# 406MHz_detector.net
KiCad netlist of a schematic drawn in EAGLE
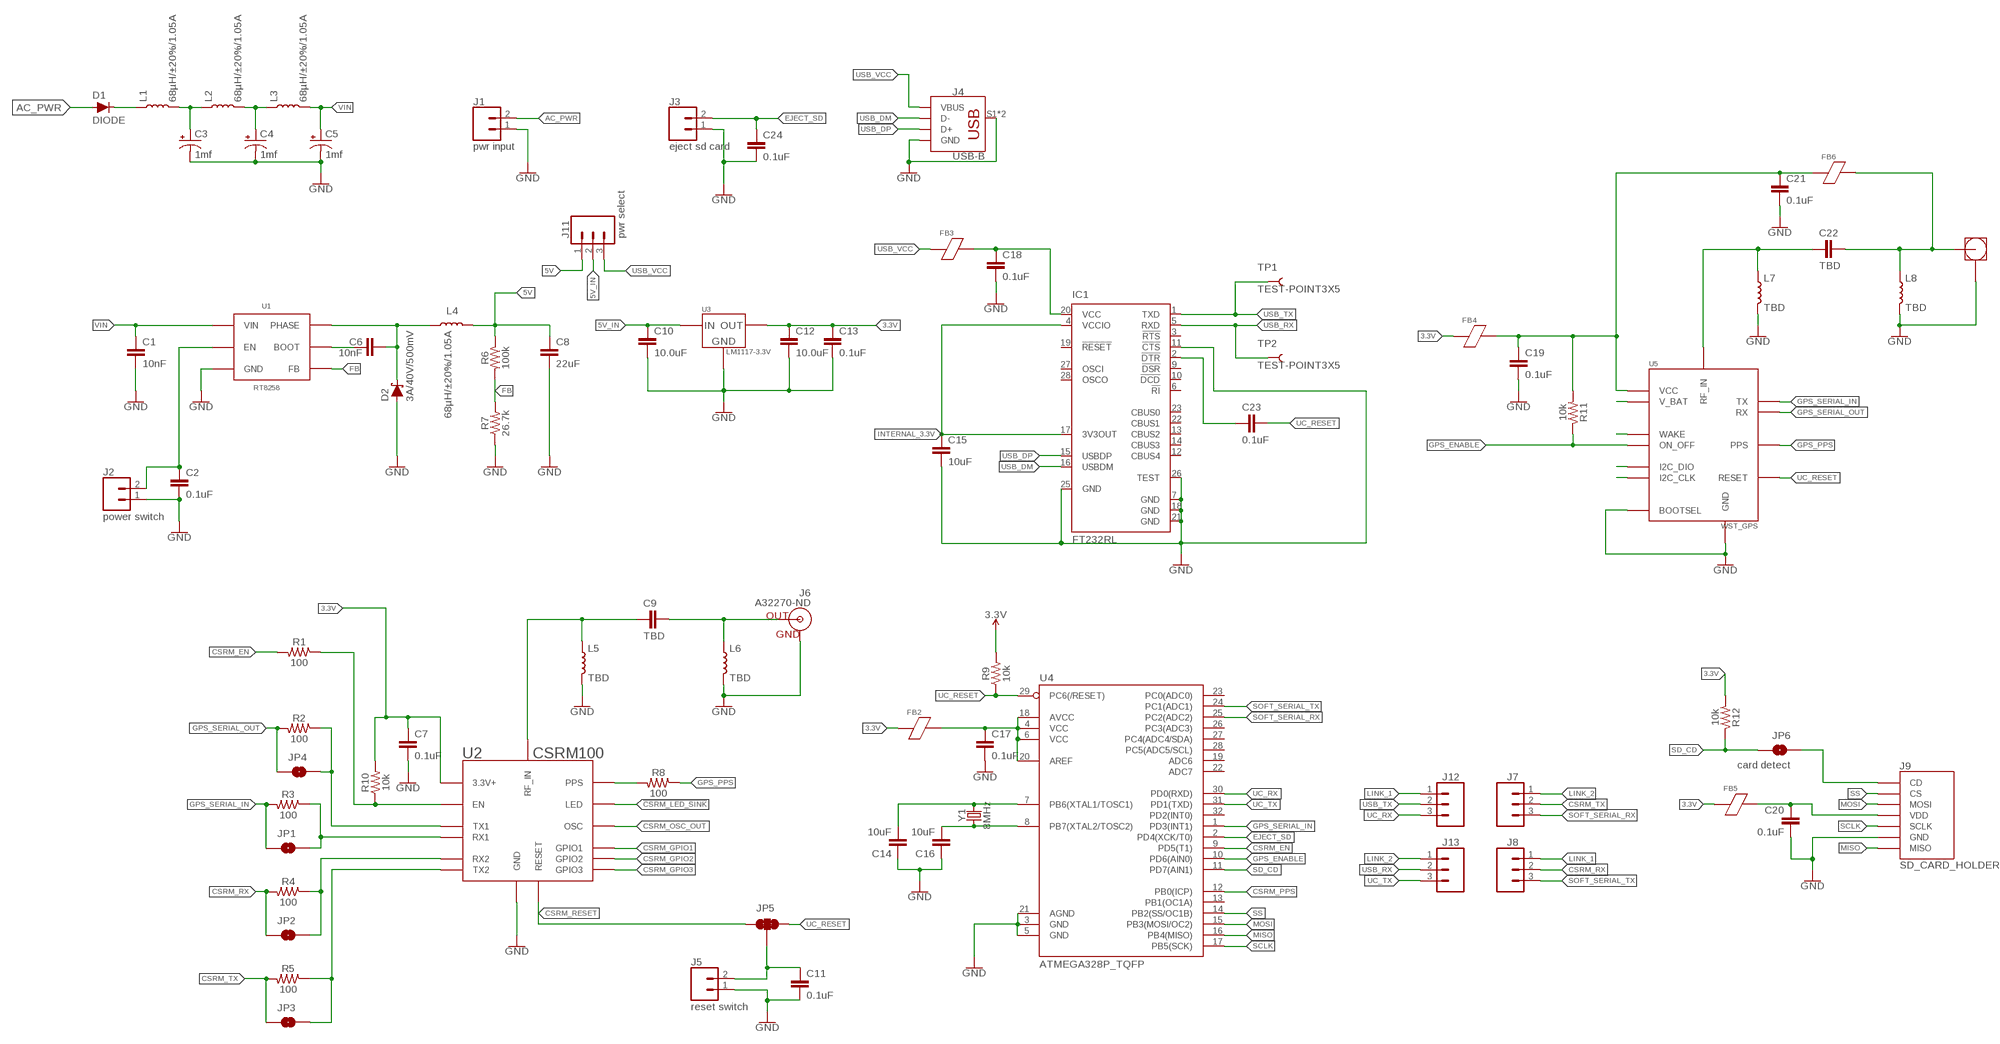
[diagram p0: schematic, sheet 1]

(export (version "E")
  (design (tool "Eeschema 10.0.6"))
  (components
    (comp (ref "C1")
      (value "10nF")
      (footprint "eagle-import:0603")
      (libsource (lib "eagle-import") (part "10NF-0603-50V-10%"))
    )
    (comp (ref "C2")
      (value "0.1uF")
      (footprint "eagle-import:0603")
      (libsource (lib "eagle-import") (part "0.18UF-0603-10V-10%"))
    )
    (comp (ref "C3")
      (value "1mf")
      (footprint "eagle-import:CPOL-RADIAL-5MM-10MM-KIT")
      (libsource (lib "eagle-import") (part "1000UF-RADIAL-5MM-35V-20%-KIT"))
    )
    (comp (ref "C4")
      (value "1mf")
      (footprint "eagle-import:CPOL-RADIAL-5MM-10MM-KIT")
      (libsource (lib "eagle-import") (part "1000UF-RADIAL-5MM-35V-20%-KIT"))
    )
    (comp (ref "C5")
      (value "1mf")
      (footprint "eagle-import:CPOL-RADIAL-5MM-10MM-KIT")
      (libsource (lib "eagle-import") (part "1000UF-RADIAL-5MM-35V-20%-KIT"))
    )
    (comp (ref "C6")
      (value "10nF")
      (footprint "eagle-import:0603")
      (libsource (lib "eagle-import") (part "10NF-0603-50V-10%"))
    )
    (comp (ref "C7")
      (value "0.1uF")
      (footprint "eagle-import:0603")
      (libsource (lib "eagle-import") (part "0.18UF-0603-10V-10%"))
    )
    (comp (ref "C8")
      (value "22uF")
      (footprint "eagle-import:0603")
      (libsource (lib "eagle-import") (part "0.18UF-0603-10V-10%"))
    )
    (comp (ref "C9")
      (value "TBD")
      (footprint "eagle-import:0603")
      (libsource (lib "eagle-import") (part "0.1UF-0603-25V-5%"))
    )
    (comp (ref "C10")
      (value "10.0uF")
      (footprint "eagle-import:1206")
      (libsource (lib "eagle-import") (part "1.0UF-1206-50V-10%"))
    )
    (comp (ref "C11")
      (value "0.1uF")
      (footprint "eagle-import:0603")
      (libsource (lib "eagle-import") (part "0.18UF-0603-10V-10%"))
    )
    (comp (ref "C12")
      (value "10.0uF")
      (footprint "eagle-import:1206")
      (libsource (lib "eagle-import") (part "1.0UF-1206-50V-10%"))
    )
    (comp (ref "C13")
      (value "0.1uF")
      (footprint "eagle-import:0603")
      (libsource (lib "eagle-import") (part "0.18UF-0603-10V-10%"))
    )
    (comp (ref "C14")
      (value "10uF")
      (footprint "eagle-import:1206")
      (libsource (lib "eagle-import") (part "10UF-1206-6.3V-20%"))
    )
    (comp (ref "C15")
      (value "10uF")
      (footprint "eagle-import:1206")
      (libsource (lib "eagle-import") (part "10UF-1206-6.3V-20%"))
    )
    (comp (ref "C16")
      (value "10uF")
      (footprint "eagle-import:1206")
      (libsource (lib "eagle-import") (part "10UF-1206-6.3V-20%"))
    )
    (comp (ref "C17")
      (value "0.1uF")
      (footprint "eagle-import:0603")
      (libsource (lib "eagle-import") (part "0.18UF-0603-10V-10%"))
    )
    (comp (ref "C18")
      (value "0.1uF")
      (footprint "eagle-import:0603")
      (libsource (lib "eagle-import") (part "0.18UF-0603-10V-10%"))
    )
    (comp (ref "C19")
      (value "0.1uF")
      (footprint "eagle-import:0603")
      (libsource (lib "eagle-import") (part "0.18UF-0603-10V-10%"))
    )
    (comp (ref "C20")
      (value "0.1uF")
      (footprint "eagle-import:0603")
      (libsource (lib "eagle-import") (part "0.18UF-0603-10V-10%"))
    )
    (comp (ref "C21")
      (value "0.1uF")
      (footprint "eagle-import:0603")
      (libsource (lib "eagle-import") (part "0.18UF-0603-10V-10%"))
    )
    (comp (ref "C22")
      (value "TBD")
      (footprint "eagle-import:0603")
      (libsource (lib "eagle-import") (part "0.1UF-0603-25V-5%"))
    )
    (comp (ref "C23")
      (value "0.1uF")
      (footprint "eagle-import:0603")
      (libsource (lib "eagle-import") (part "0.18UF-0603-10V-10%"))
    )
    (comp (ref "C24")
      (value "0.1uF")
      (footprint "eagle-import:0603")
      (libsource (lib "eagle-import") (part "0.18UF-0603-10V-10%"))
    )
    (comp (ref "D1")
      (value "DIODE")
      (footprint "eagle-import:SMA-DIODE")
      (libsource (lib "eagle-import") (part "DIODE"))
    )
    (comp (ref "D2")
      (value "3A/40V/500mV")
      (footprint "eagle-import:SMA-DIODE")
      (libsource (lib "eagle-import") (part "DIODE-SCHOTTKY-B340A"))
    )
    (comp (ref "FB2")
      (value "FERRITE_BEAD")
      (footprint "eagle-import:0603")
      (libsource (lib "eagle-import") (part "FERRITE_BEAD"))
    )
    (comp (ref "FB3")
      (value "FERRITE_BEAD")
      (footprint "eagle-import:0603")
      (libsource (lib "eagle-import") (part "FERRITE_BEAD"))
    )
    (comp (ref "FB4")
      (value "FERRITE_BEAD")
      (footprint "eagle-import:0603")
      (libsource (lib "eagle-import") (part "FERRITE_BEAD"))
    )
    (comp (ref "FB5")
      (value "FERRITE_BEAD")
      (footprint "eagle-import:0603")
      (libsource (lib "eagle-import") (part "FERRITE_BEAD"))
    )
    (comp (ref "FB6")
      (value "FERRITE_BEAD")
      (footprint "eagle-import:0603")
      (libsource (lib "eagle-import") (part "FERRITE_BEAD"))
    )
    (comp (ref "IC1")
      (value "FT232RL")
      (footprint "eagle-import:SSOP28")
      (libsource (lib "eagle-import") (part "FT232RL"))
    )
    (comp (ref "J1")
      (value "pwr input")
      (footprint "eagle-import:1X02_LOCK")
      (libsource (lib "eagle-import") (part "CONN_02LOCK"))
    )
    (comp (ref "J2")
      (value "power switch")
      (footprint "eagle-import:1X02")
      (libsource (lib "eagle-import") (part "CONN_02"))
    )
    (comp (ref "J3")
      (value "eject sd card")
      (footprint "eagle-import:1X02")
      (libsource (lib "eagle-import") (part "CONN_02"))
    )
    (comp (ref "J4")
      (value "USB-B")
      (footprint "eagle-import:USB")
      (libsource (lib "eagle-import") (part "USB-B"))
    )
    (comp (ref "J5")
      (value "reset switch")
      (footprint "eagle-import:1X02")
      (libsource (lib "eagle-import") (part "CONN_02"))
    )
    (comp (ref "J6")
      (value "A32270-ND")
      (footprint "eagle-import:A33270-ND")
      (libsource (lib "eagle-import") (part "A32270-ND"))
    )
    (comp (ref "J7")
      (value "select jumper")
      (footprint "eagle-import:1X03_LOCK")
      (libsource (lib "eagle-import") (part "CONN_03LOCK"))
    )
    (comp (ref "J8")
      (value "select jumper")
      (footprint "eagle-import:1X03_LOCK")
      (libsource (lib "eagle-import") (part "CONN_03LOCK"))
    )
    (comp (ref "J9")
      (value "SD_CARD_HOLDER")
      (footprint "eagle-import:SD_CARD_HOLDER")
      (libsource (lib "eagle-import") (part "SD_CARD_HOLDER"))
    )
    (comp (ref "J10")
      (value "SMA")
      (footprint "eagle-import:SMA_R_A")
      (libsource (lib "eagle-import") (part "SMA"))
    )
    (comp (ref "J11")
      (value "pwr select")
      (footprint "eagle-import:1X03_LOCK")
      (libsource (lib "eagle-import") (part "CONN_03LOCK"))
    )
    (comp (ref "J12")
      (value "select jumper")
      (footprint "eagle-import:1X03_LOCK")
      (libsource (lib "eagle-import") (part "CONN_03LOCK"))
    )
    (comp (ref "J13")
      (value "select jumper")
      (footprint "eagle-import:1X03_LOCK")
      (libsource (lib "eagle-import") (part "CONN_03LOCK"))
    )
    (comp (ref "JP1")
      (value "JUMPER-SMT_2_NO_SILK_ROUND")
      (footprint "eagle-import:SMT-JUMPER_2_NO_SILK_ROUND")
      (libsource (lib "eagle-import") (part "JUMPER-SMT_2_NO_SILK_ROUND"))
    )
    (comp (ref "JP2")
      (value "JUMPER-SMT_2_NO_SILK_ROUND")
      (footprint "eagle-import:SMT-JUMPER_2_NO_SILK_ROUND")
      (libsource (lib "eagle-import") (part "JUMPER-SMT_2_NO_SILK_ROUND"))
    )
    (comp (ref "JP3")
      (value "JUMPER-SMT_2_NO_SILK_ROUND")
      (footprint "eagle-import:SMT-JUMPER_2_NO_SILK_ROUND")
      (libsource (lib "eagle-import") (part "JUMPER-SMT_2_NO_SILK_ROUND"))
    )
    (comp (ref "JP4")
      (value "JUMPER-SMT_2_NO_SILK_ROUND")
      (footprint "eagle-import:SMT-JUMPER_2_NO_SILK_ROUND")
      (libsource (lib "eagle-import") (part "JUMPER-SMT_2_NO_SILK_ROUND"))
    )
    (comp (ref "JP5")
      (value "JUMPER-SMT_3_2-NC_TRACE_SILK")
      (footprint "eagle-import:SMT-JUMPER_3_2-NC_TRACE_SILK")
      (libsource (lib "eagle-import") (part "JUMPER-SMT_3_2-NC_TRACE_SILK"))
    )
    (comp (ref "JP6")
      (value "card detect")
      (footprint "eagle-import:SMT-JUMPER_2_NO_SILK")
      (libsource (lib "eagle-import") (part "JUMPER-SMT_2_NO_SILK"))
    )
    (comp (ref "L1")
      (value "68µH/±20%/1.05A")
      (footprint "eagle-import:CR75")
      (libsource (lib "eagle-import") (part "INDUCTOR-CR75-68UH"))
    )
    (comp (ref "L2")
      (value "68µH/±20%/1.05A")
      (footprint "eagle-import:CR75")
      (libsource (lib "eagle-import") (part "INDUCTOR-CR75-68UH"))
    )
    (comp (ref "L3")
      (value "68µH/±20%/1.05A")
      (footprint "eagle-import:CR75")
      (libsource (lib "eagle-import") (part "INDUCTOR-CR75-68UH"))
    )
    (comp (ref "L4")
      (value "68µH/±20%/1.05A")
      (footprint "eagle-import:CR75")
      (libsource (lib "eagle-import") (part "INDUCTOR-CR75-68UH"))
    )
    (comp (ref "L5")
      (value "TBD")
      (footprint "eagle-import:0603")
      (libsource (lib "eagle-import") (part "INDUCTOR-0603-33NH"))
    )
    (comp (ref "L6")
      (value "TBD")
      (footprint "eagle-import:0603")
      (libsource (lib "eagle-import") (part "INDUCTOR-0603-33NH"))
    )
    (comp (ref "L7")
      (value "TBD")
      (footprint "eagle-import:0603")
      (libsource (lib "eagle-import") (part "INDUCTOR-0603-33NH"))
    )
    (comp (ref "L8")
      (value "TBD")
      (footprint "eagle-import:0603")
      (libsource (lib "eagle-import") (part "INDUCTOR-0603-33NH"))
    )
    (comp (ref "R1")
      (value "100")
      (footprint "eagle-import:0603")
      (libsource (lib "eagle-import") (part "10KOHM-0603-1/10W-1%"))
    )
    (comp (ref "R2")
      (value "100")
      (footprint "eagle-import:0603")
      (libsource (lib "eagle-import") (part "10KOHM-0603-1/10W-1%"))
    )
    (comp (ref "R3")
      (value "100")
      (footprint "eagle-import:0603")
      (libsource (lib "eagle-import") (part "10KOHM-0603-1/10W-1%"))
    )
    (comp (ref "R4")
      (value "100")
      (footprint "eagle-import:0603")
      (libsource (lib "eagle-import") (part "10KOHM-0603-1/10W-1%"))
    )
    (comp (ref "R5")
      (value "100")
      (footprint "eagle-import:0603")
      (libsource (lib "eagle-import") (part "10KOHM-0603-1/10W-1%"))
    )
    (comp (ref "R6")
      (value "100k")
      (footprint "eagle-import:0603")
      (libsource (lib "eagle-import") (part "10KOHM-0603-1/10W-1%"))
    )
    (comp (ref "R7")
      (value "26.7k")
      (footprint "eagle-import:0603")
      (libsource (lib "eagle-import") (part "26.7KOHM0603-1/10W-1%"))
    )
    (comp (ref "R8")
      (value "100")
      (footprint "eagle-import:0603")
      (libsource (lib "eagle-import") (part "10KOHM-0603-1/10W-1%"))
    )
    (comp (ref "R9")
      (value "10k")
      (footprint "eagle-import:0603")
      (libsource (lib "eagle-import") (part "10KOHM-0603-1/10W-1%"))
    )
    (comp (ref "R10")
      (value "10k")
      (footprint "eagle-import:0603")
      (libsource (lib "eagle-import") (part "10KOHM-0603-1/10W-1%"))
    )
    (comp (ref "R11")
      (value "10k")
      (footprint "eagle-import:0603")
      (libsource (lib "eagle-import") (part "10KOHM-0603-1/10W-1%"))
    )
    (comp (ref "R12")
      (value "10k")
      (footprint "eagle-import:0603")
      (libsource (lib "eagle-import") (part "10KOHM-0603-1/10W-1%"))
    )
    (comp (ref "TP1")
      (value "TEST-POINT3X5")
      (footprint "eagle-import:PAD.03X.05")
      (libsource (lib "eagle-import") (part "TEST-POINT3X5"))
    )
    (comp (ref "TP2")
      (value "TEST-POINT3X5")
      (footprint "eagle-import:PAD.03X.05")
      (libsource (lib "eagle-import") (part "TEST-POINT3X5"))
    )
    (comp (ref "U1")
      (value "RT8258")
      (footprint "eagle-import:SOT23-6")
      (libsource (lib "eagle-import") (part "RT8258"))
    )
    (comp (ref "U2")
      (value "CSRM100")
      (footprint "eagle-import:CSRM")
      (libsource (lib "eagle-import") (part "CSRM100"))
    )
    (comp (ref "U3")
      (value "LM1117-3.3V")
      (footprint "eagle-import:SOT223")
      (libsource (lib "eagle-import") (part "LM1117-3.3V"))
    )
    (comp (ref "U4")
      (value "ATMEGA328P_TQFP")
      (footprint "eagle-import:TQFP32-08")
      (libsource (lib "eagle-import") (part "ATMEGA328P_TQFP"))
    )
    (comp (ref "U5")
      (value "WST_GPS")
      (footprint "eagle-import:WST_GPS")
      (libsource (lib "eagle-import") (part "WST_GPS"))
    )
    (comp (ref "Y1")
      (value "8MHz")
      (footprint "eagle-import:HC49UP")
      (libsource (lib "eagle-import") (part "CRYSTAL-8MHZSMD-HC49UP"))
    )
  )
  (nets
    (net (code "1") (name "/~{CSRM_LED_SINK}") (class "Default")
      (node (ref "U2") (pin "LED") (pinfunction "LED_LED") (pintype "bidirectional"))
    )
    (net (code "2") (name "3.3V") (class "Default")
      (node (ref "C12") (pin "1") (pinfunction "1_1") (pintype "passive"))
      (node (ref "C13") (pin "1") (pinfunction "1_1") (pintype "passive"))
      (node (ref "C7") (pin "1") (pinfunction "1_1") (pintype "passive"))
      (node (ref "FB2") (pin "1") (pinfunction "P$1_1") (pintype "bidirectional"))
      (node (ref "FB4") (pin "1") (pinfunction "P$1_1") (pintype "bidirectional"))
      (node (ref "FB5") (pin "1") (pinfunction "P$1_1") (pintype "bidirectional"))
      (node (ref "R10") (pin "2") (pinfunction "2_2") (pintype "passive"))
      (node (ref "R12") (pin "2") (pinfunction "2_2") (pintype "passive"))
      (node (ref "R9") (pin "2") (pinfunction "2_2") (pintype "passive"))
      (node (ref "U2") (pin "PWR_IN") (pinfunction "3.3V+_PWR_IN") (pintype "bidirectional"))
      (node (ref "U3") (pin "2") (pinfunction "VOUT_2") (pintype "bidirectional"))
      (node (ref "U3") (pin "4") (pinfunction "VOUT_4") (pintype "bidirectional"))
    )
    (net (code "3") (name "5V") (class "Default")
      (node (ref "C8") (pin "1") (pinfunction "1_1") (pintype "passive"))
      (node (ref "J11") (pin "1") (pinfunction "1_1") (pintype "passive"))
      (node (ref "L4") (pin "P$2") (pinfunction "2_P$2") (pintype "passive"))
      (node (ref "R6") (pin "1") (pinfunction "1_1") (pintype "passive"))
    )
    (net (code "4") (name "5V_IN") (class "Default")
      (node (ref "C10") (pin "1") (pinfunction "1_1") (pintype "passive"))
      (node (ref "J11") (pin "2") (pinfunction "2_2") (pintype "passive"))
      (node (ref "U3") (pin "3") (pinfunction "VIN_3") (pintype "bidirectional"))
    )
    (net (code "5") (name "AC_PWR") (class "Default")
      (node (ref "D1") (pin "A") (pinfunction "A_A") (pintype "passive"))
      (node (ref "J1") (pin "2") (pinfunction "2_2") (pintype "passive"))
    )
    (net (code "6") (name "CSRM_EN") (class "Default")
      (node (ref "R1") (pin "2") (pinfunction "2_2") (pintype "passive"))
      (node (ref "U4") (pin "9") (pinfunction "PD5(T1)_9") (pintype "bidirectional"))
    )
    (net (code "7") (name "CSRM_GPIO1") (class "Default")
      (node (ref "U2") (pin "GPIO1") (pinfunction "GPIO1_GPIO1") (pintype "bidirectional"))
    )
    (net (code "8") (name "CSRM_GPIO2") (class "Default")
      (node (ref "U2") (pin "GPIO2") (pinfunction "GPIO2_GPIO2") (pintype "bidirectional"))
    )
    (net (code "9") (name "CSRM_GPIO3") (class "Default")
      (node (ref "U2") (pin "GPIO3") (pinfunction "GPIO3_GPIO3") (pintype "bidirectional"))
    )
    (net (code "10") (name "CSRM_OSC_OUT") (class "Default")
      (node (ref "U2") (pin "OSC_OUT") (pinfunction "OSC_OSC_OUT") (pintype "bidirectional"))
    )
    (net (code "11") (name "CSRM_PPS") (class "Default")
      (node (ref "R8") (pin "2") (pinfunction "2_2") (pintype "passive"))
      (node (ref "U2") (pin "PPS") (pinfunction "PPS_PPS") (pintype "bidirectional"))
      (node (ref "U4") (pin "12") (pinfunction "PB0(ICP)_12") (pintype "bidirectional"))
    )
    (net (code "12") (name "CSRM_RESET") (class "Default")
      (node (ref "JP5") (pin "1") (pinfunction "1_1") (pintype "passive"))
      (node (ref "U2") (pin "_RESET") (pinfunction "RESET__RESET") (pintype "bidirectional"))
    )
    (net (code "13") (name "CSRM_RX") (class "Default")
      (node (ref "J8") (pin "2") (pinfunction "2_2") (pintype "passive"))
      (node (ref "JP2") (pin "1") (pinfunction "1_1") (pintype "passive"))
      (node (ref "R4") (pin "2") (pinfunction "2_2") (pintype "passive"))
    )
    (net (code "14") (name "CSRM_TX") (class "Default")
      (node (ref "J7") (pin "2") (pinfunction "2_2") (pintype "passive"))
      (node (ref "JP3") (pin "1") (pinfunction "1_1") (pintype "passive"))
      (node (ref "R5") (pin "2") (pinfunction "2_2") (pintype "passive"))
    )
    (net (code "15") (name "EJECT_SD") (class "Default")
      (node (ref "C24") (pin "1") (pinfunction "1_1") (pintype "passive"))
      (node (ref "J3") (pin "2") (pinfunction "2_2") (pintype "passive"))
      (node (ref "U4") (pin "2") (pinfunction "PD4(XCK/T0)_2") (pintype "bidirectional"))
    )
    (net (code "16") (name "FB") (class "Default")
      (node (ref "R6") (pin "2") (pinfunction "2_2") (pintype "passive"))
      (node (ref "R7") (pin "2") (pinfunction "2_2") (pintype "passive"))
      (node (ref "U1") (pin "3") (pinfunction "FB_3") (pintype "bidirectional"))
    )
    (net (code "17") (name "GND") (class "Default")
      (node (ref "C1") (pin "2") (pinfunction "2_2") (pintype "passive"))
      (node (ref "C10") (pin "2") (pinfunction "2_2") (pintype "passive"))
      (node (ref "C11") (pin "2") (pinfunction "2_2") (pintype "passive"))
      (node (ref "C12") (pin "2") (pinfunction "2_2") (pintype "passive"))
      (node (ref "C13") (pin "2") (pinfunction "2_2") (pintype "passive"))
      (node (ref "C14") (pin "1") (pinfunction "1_1") (pintype "passive"))
      (node (ref "C15") (pin "2") (pinfunction "2_2") (pintype "passive"))
      (node (ref "C16") (pin "1") (pinfunction "1_1") (pintype "passive"))
      (node (ref "C17") (pin "2") (pinfunction "2_2") (pintype "passive"))
      (node (ref "C18") (pin "2") (pinfunction "2_2") (pintype "passive"))
      (node (ref "C19") (pin "2") (pinfunction "2_2") (pintype "passive"))
      (node (ref "C2") (pin "2") (pinfunction "2_2") (pintype "passive"))
      (node (ref "C20") (pin "2") (pinfunction "2_2") (pintype "passive"))
      (node (ref "C21") (pin "2") (pinfunction "2_2") (pintype "passive"))
      (node (ref "C24") (pin "2") (pinfunction "2_2") (pintype "passive"))
      (node (ref "C3") (pin "-") (pinfunction "-_-") (pintype "passive"))
      (node (ref "C4") (pin "-") (pinfunction "-_-") (pintype "passive"))
      (node (ref "C5") (pin "-") (pinfunction "-_-") (pintype "passive"))
      (node (ref "C7") (pin "2") (pinfunction "2_2") (pintype "passive"))
      (node (ref "C8") (pin "2") (pinfunction "2_2") (pintype "passive"))
      (node (ref "D2") (pin "A") (pinfunction "A_A") (pintype "passive"))
      (node (ref "IC1") (pin "11") (pinfunction "~{CTS}_11") (pintype "input"))
      (node (ref "IC1") (pin "18") (pinfunction "GND_18") (pintype "power_in"))
      (node (ref "IC1") (pin "21") (pinfunction "GND_21") (pintype "power_in"))
      (node (ref "IC1") (pin "25") (pinfunction "GND_25") (pintype "power_in"))
      (node (ref "IC1") (pin "26") (pinfunction "TEST_26") (pintype "input"))
      (node (ref "IC1") (pin "7") (pinfunction "GND_7") (pintype "power_in"))
      (node (ref "J1") (pin "1") (pinfunction "1_1") (pintype "passive"))
      (node (ref "J10") (pin "P$2") (pinfunction "P$2_P$2") (pintype "bidirectional"))
      (node (ref "J10") (pin "P$3") (pinfunction "P$2_P$3") (pintype "bidirectional"))
      (node (ref "J10") (pin "P$4") (pinfunction "P$2_P$4") (pintype "bidirectional"))
      (node (ref "J10") (pin "P$5") (pinfunction "P$2_P$5") (pintype "bidirectional"))
      (node (ref "J2") (pin "1") (pinfunction "1_1") (pintype "passive"))
      (node (ref "J3") (pin "1") (pinfunction "1_1") (pintype "passive"))
      (node (ref "J4") (pin "4") (pinfunction "GND_4") (pintype "power_in"))
      (node (ref "J4") (pin "S1") (pinfunction "SHIELD_S1") (pintype "bidirectional"))
      (node (ref "J4") (pin "S2") (pinfunction "SHIELD_S2") (pintype "bidirectional"))
      (node (ref "J5") (pin "1") (pinfunction "1_1") (pintype "passive"))
      (node (ref "J6") (pin "GND1") (pinfunction "GND_GND1") (pintype "bidirectional"))
      (node (ref "J6") (pin "GND2") (pinfunction "GND_GND2") (pintype "bidirectional"))
      (node (ref "J6") (pin "GND3") (pinfunction "GND_GND3") (pintype "bidirectional"))
      (node (ref "J6") (pin "GND4") (pinfunction "GND_GND4") (pintype "bidirectional"))
      (node (ref "J9") (pin "GND1") (pinfunction "GND_GND1") (pintype "bidirectional"))
      (node (ref "J9") (pin "GND2") (pinfunction "GND_GND2") (pintype "bidirectional"))
      (node (ref "J9") (pin "P6") (pinfunction "GND_P6") (pintype "bidirectional"))
      (node (ref "L5") (pin "2") (pinfunction "2_2") (pintype "passive"))
      (node (ref "L6") (pin "2") (pinfunction "2_2") (pintype "passive"))
      (node (ref "L7") (pin "2") (pinfunction "2_2") (pintype "passive"))
      (node (ref "L8") (pin "2") (pinfunction "2_2") (pintype "passive"))
      (node (ref "R7") (pin "1") (pinfunction "1_1") (pintype "passive"))
      (node (ref "U1") (pin "2") (pinfunction "GND_2") (pintype "bidirectional"))
      (node (ref "U2") (pin "GND") (pinfunction "GND_GND") (pintype "bidirectional"))
      (node (ref "U2") (pin "GND1") (pinfunction "GND_GND1") (pintype "bidirectional"))
      (node (ref "U2") (pin "GND2") (pinfunction "GND_GND2") (pintype "bidirectional"))
      (node (ref "U2") (pin "GND3") (pinfunction "GND_GND3") (pintype "bidirectional"))
      (node (ref "U2") (pin "GND4") (pinfunction "GND_GND4") (pintype "bidirectional"))
      (node (ref "U3") (pin "1") (pinfunction "GND_1") (pintype "bidirectional"))
      (node (ref "U4") (pin "21") (pinfunction "AGND_21") (pintype "bidirectional"))
      (node (ref "U4") (pin "3") (pinfunction "GND_3") (pintype "bidirectional"))
      (node (ref "U4") (pin "5") (pinfunction "GND_5") (pintype "bidirectional"))
      (node (ref "U5") (pin "P$1") (pinfunction "GND_P$1") (pintype "bidirectional"))
      (node (ref "U5") (pin "P$17") (pinfunction "GND_P$17") (pintype "bidirectional"))
      (node (ref "U5") (pin "P$18") (pinfunction "GND_P$18") (pintype "bidirectional"))
      (node (ref "U5") (pin "P$19") (pinfunction "GND_P$19") (pintype "bidirectional"))
      (node (ref "U5") (pin "P$3") (pinfunction "GND_P$3") (pintype "bidirectional"))
      (node (ref "U5") (pin "P$9") (pinfunction "BOOTSEL_P$9") (pintype "bidirectional"))
    )
    (net (code "18") (name "GPS_ENABLE") (class "Default")
      (node (ref "R11") (pin "1") (pinfunction "1_1") (pintype "passive"))
      (node (ref "U4") (pin "10") (pinfunction "PD6(AIN0)_10") (pintype "bidirectional"))
      (node (ref "U5") (pin "P$15") (pinfunction "ON_OFF_P$15") (pintype "bidirectional"))
    )
    (net (code "19") (name "GPS_PPS") (class "Default")
      (node (ref "R8") (pin "1") (pinfunction "1_1") (pintype "passive"))
      (node (ref "U5") (pin "P$14") (pinfunction "PPS_P$14") (pintype "bidirectional"))
    )
    (net (code "20") (name "GPS_SERIAL_IN") (class "Default")
      (node (ref "JP1") (pin "1") (pinfunction "1_1") (pintype "passive"))
      (node (ref "R3") (pin "2") (pinfunction "2_2") (pintype "passive"))
      (node (ref "U4") (pin "1") (pinfunction "PD3(INT1)_1") (pintype "bidirectional"))
      (node (ref "U5") (pin "P$10") (pinfunction "TX_P$10") (pintype "bidirectional"))
    )
    (net (code "21") (name "GPS_SERIAL_OUT") (class "Default")
      (node (ref "JP4") (pin "1") (pinfunction "1_1") (pintype "passive"))
      (node (ref "R2") (pin "2") (pinfunction "2_2") (pintype "passive"))
      (node (ref "U5") (pin "P$11") (pinfunction "RX_P$11") (pintype "bidirectional"))
    )
    (net (code "22") (name "INTERNAL_3.3V") (class "Default")
      (node (ref "C15") (pin "1") (pinfunction "1_1") (pintype "passive"))
      (node (ref "IC1") (pin "17") (pinfunction "3V3OUT_17") (pintype "output"))
      (node (ref "IC1") (pin "4") (pinfunction "VCCIO_4") (pintype "power_in"))
    )
    (net (code "23") (name "LINK_1") (class "Default")
      (node (ref "J12") (pin "1") (pinfunction "1_1") (pintype "passive"))
      (node (ref "J8") (pin "1") (pinfunction "1_1") (pintype "passive"))
    )
    (net (code "24") (name "LINK_2") (class "Default")
      (node (ref "J13") (pin "1") (pinfunction "1_1") (pintype "passive"))
      (node (ref "J7") (pin "1") (pinfunction "1_1") (pintype "passive"))
    )
    (net (code "25") (name "MISO") (class "Default")
      (node (ref "J9") (pin "P7") (pinfunction "MISO_P7") (pintype "bidirectional"))
      (node (ref "U4") (pin "16") (pinfunction "PB4(MISO)_16") (pintype "bidirectional"))
    )
    (net (code "26") (name "MOSI") (class "Default")
      (node (ref "J9") (pin "P3") (pinfunction "MOSI_P3") (pintype "bidirectional"))
      (node (ref "U4") (pin "15") (pinfunction "PB3(MOSI/OC2)_15") (pintype "bidirectional"))
    )
    (net (code "27") (name "Net-(C9-Pad1)") (class "Default")
      (node (ref "C9") (pin "1") (pinfunction "1_1") (pintype "passive"))
      (node (ref "J6") (pin "OUT") (pinfunction "OUT_OUT") (pintype "bidirectional"))
      (node (ref "L6") (pin "1") (pinfunction "1_1") (pintype "passive"))
    )
    (net (code "28") (name "Net-(C11-Pad1)") (class "Default")
      (node (ref "C11") (pin "1") (pinfunction "1_1") (pintype "passive"))
      (node (ref "J5") (pin "2") (pinfunction "2_2") (pintype "passive"))
      (node (ref "JP5") (pin "2") (pinfunction "2_2") (pintype "passive"))
    )
    (net (code "29") (name "Net-(FB2-P$2)") (class "Default")
      (node (ref "C17") (pin "1") (pinfunction "1_1") (pintype "passive"))
      (node (ref "FB2") (pin "2") (pinfunction "P$2_2") (pintype "bidirectional"))
      (node (ref "U4") (pin "18") (pinfunction "AVCC_18") (pintype "bidirectional"))
      (node (ref "U4") (pin "20") (pinfunction "AREF_20") (pintype "bidirectional"))
      (node (ref "U4") (pin "4") (pinfunction "VCC_4") (pintype "bidirectional"))
      (node (ref "U4") (pin "6") (pinfunction "VCC_6") (pintype "bidirectional"))
    )
    (net (code "30") (name "Net-(FB3-P$1)") (class "Default")
      (node (ref "C18") (pin "1") (pinfunction "1_1") (pintype "passive"))
      (node (ref "FB3") (pin "1") (pinfunction "P$1_1") (pintype "bidirectional"))
      (node (ref "IC1") (pin "20") (pinfunction "VCC_20") (pintype "power_in"))
    )
    (net (code "31") (name "Net-(FB4-P$2)") (class "Default")
      (node (ref "C19") (pin "1") (pinfunction "1_1") (pintype "passive"))
      (node (ref "C21") (pin "1") (pinfunction "1_1") (pintype "passive"))
      (node (ref "FB4") (pin "2") (pinfunction "P$2_2") (pintype "bidirectional"))
      (node (ref "FB6") (pin "1") (pinfunction "P$1_1") (pintype "bidirectional"))
      (node (ref "R11") (pin "2") (pinfunction "2_2") (pintype "passive"))
      (node (ref "U5") (pin "P$5") (pinfunction "VCC_P$5") (pintype "bidirectional"))
    )
    (net (code "32") (name "Net-(FB5-P$2)") (class "Default")
      (node (ref "C20") (pin "1") (pinfunction "1_1") (pintype "passive"))
      (node (ref "FB5") (pin "2") (pinfunction "P$2_2") (pintype "bidirectional"))
      (node (ref "J9") (pin "P4") (pinfunction "VDD_P4") (pintype "bidirectional"))
    )
    (net (code "33") (name "Net-(FB6-P$2)") (class "Default")
      (node (ref "C22") (pin "1") (pinfunction "1_1") (pintype "passive"))
      (node (ref "FB6") (pin "2") (pinfunction "P$2_2") (pintype "bidirectional"))
      (node (ref "J10") (pin "P$1") (pinfunction "P$1_P$1") (pintype "bidirectional"))
      (node (ref "L8") (pin "1") (pinfunction "1_1") (pintype "passive"))
    )
    (net (code "34") (name "Net-(IC1-~{DTR})") (class "Default")
      (node (ref "C23") (pin "1") (pinfunction "1_1") (pintype "passive"))
      (node (ref "IC1") (pin "2") (pinfunction "~{DTR}_2") (pintype "output"))
    )
    (net (code "35") (name "Net-(J9-CD-PadCD1)") (class "Default")
      (node (ref "J9") (pin "CD1") (pinfunction "CD_CD1") (pintype "bidirectional"))
      (node (ref "J9") (pin "CD2") (pinfunction "CD_CD2") (pintype "bidirectional"))
      (node (ref "JP6") (pin "1") (pinfunction "1_1") (pintype "passive"))
    )
    (net (code "36") (name "Net-(JP1-Pad2)") (class "Default")
      (node (ref "JP1") (pin "2") (pinfunction "2_2") (pintype "passive"))
      (node (ref "R3") (pin "1") (pinfunction "1_1") (pintype "passive"))
      (node (ref "U2") (pin "RX1") (pinfunction "RX1_RX1") (pintype "bidirectional"))
    )
    (net (code "37") (name "Net-(JP2-Pad2)") (class "Default")
      (node (ref "JP2") (pin "2") (pinfunction "2_2") (pintype "passive"))
      (node (ref "R4") (pin "1") (pinfunction "1_1") (pintype "passive"))
      (node (ref "U2") (pin "RX2") (pinfunction "RX2_RX2") (pintype "bidirectional"))
    )
    (net (code "38") (name "Net-(JP3-Pad2)") (class "Default")
      (node (ref "JP3") (pin "2") (pinfunction "2_2") (pintype "passive"))
      (node (ref "R5") (pin "1") (pinfunction "1_1") (pintype "passive"))
      (node (ref "U2") (pin "TX2") (pinfunction "TX2_TX2") (pintype "bidirectional"))
    )
    (net (code "39") (name "Net-(JP4-Pad2)") (class "Default")
      (node (ref "JP4") (pin "2") (pinfunction "2_2") (pintype "passive"))
      (node (ref "R2") (pin "1") (pinfunction "1_1") (pintype "passive"))
      (node (ref "U2") (pin "TX1") (pinfunction "TX1_TX1") (pintype "bidirectional"))
    )
    (net (code "40") (name "Net-(L1-1)") (class "Default")
      (node (ref "D1") (pin "C") (pinfunction "C_C") (pintype "passive"))
      (node (ref "L1") (pin "P$1") (pinfunction "1_P$1") (pintype "passive"))
    )
    (net (code "41") (name "Net-(L1-2)") (class "Default")
      (node (ref "C3") (pin "+") (pinfunction "+_+") (pintype "passive"))
      (node (ref "L1") (pin "P$2") (pinfunction "2_P$2") (pintype "passive"))
      (node (ref "L2") (pin "P$1") (pinfunction "1_P$1") (pintype "passive"))
    )
    (net (code "42") (name "Net-(L2-2)") (class "Default")
      (node (ref "C4") (pin "+") (pinfunction "+_+") (pintype "passive"))
      (node (ref "L2") (pin "P$2") (pinfunction "2_P$2") (pintype "passive"))
      (node (ref "L3") (pin "P$1") (pinfunction "1_P$1") (pintype "passive"))
    )
    (net (code "43") (name "Net-(L4-1)") (class "Default")
      (node (ref "C6") (pin "2") (pinfunction "2_2") (pintype "passive"))
      (node (ref "D2") (pin "C") (pinfunction "C_C") (pintype "passive"))
      (node (ref "L4") (pin "P$1") (pinfunction "1_P$1") (pintype "passive"))
      (node (ref "U1") (pin "6") (pinfunction "PHASE_6") (pintype "bidirectional"))
    )
    (net (code "44") (name "Net-(R1-Pad1)") (class "Default")
      (node (ref "R1") (pin "1") (pinfunction "1_1") (pintype "passive"))
      (node (ref "R10") (pin "1") (pinfunction "1_1") (pintype "passive"))
      (node (ref "U2") (pin "EN") (pinfunction "EN_EN") (pintype "bidirectional"))
    )
    (net (code "45") (name "Net-(U1-BOOT)") (class "Default")
      (node (ref "C6") (pin "1") (pinfunction "1_1") (pintype "passive"))
      (node (ref "U1") (pin "1") (pinfunction "BOOT_1") (pintype "bidirectional"))
    )
    (net (code "46") (name "Net-(U1-EN)") (class "Default")
      (node (ref "C2") (pin "1") (pinfunction "1_1") (pintype "passive"))
      (node (ref "J2") (pin "2") (pinfunction "2_2") (pintype "passive"))
      (node (ref "U1") (pin "4") (pinfunction "EN_4") (pintype "bidirectional"))
    )
    (net (code "47") (name "Net-(U2-RF_IN)") (class "Default")
      (node (ref "C9") (pin "2") (pinfunction "2_2") (pintype "passive"))
      (node (ref "L5") (pin "1") (pinfunction "1_1") (pintype "passive"))
      (node (ref "U2") (pin "406_IN") (pinfunction "RF_IN_406_IN") (pintype "bidirectional"))
    )
    (net (code "48") (name "Net-(U4-PB6(XTAL1{slash}TOSC1))") (class "Default")
      (node (ref "C14") (pin "2") (pinfunction "2_2") (pintype "passive"))
      (node (ref "U4") (pin "7") (pinfunction "PB6(XTAL1/TOSC1)_7") (pintype "bidirectional"))
      (node (ref "Y1") (pin "2") (pinfunction "2_2") (pintype "passive"))
    )
    (net (code "49") (name "Net-(U4-PB7(XTAL2{slash}TOSC2))") (class "Default")
      (node (ref "C16") (pin "2") (pinfunction "2_2") (pintype "passive"))
      (node (ref "U4") (pin "8") (pinfunction "PB7(XTAL2/TOSC2)_8") (pintype "bidirectional"))
      (node (ref "Y1") (pin "1") (pinfunction "1_1") (pintype "passive"))
    )
    (net (code "50") (name "Net-(U5-RF_IN)") (class "Default")
      (node (ref "C22") (pin "2") (pinfunction "2_2") (pintype "passive"))
      (node (ref "L7") (pin "1") (pinfunction "1_1") (pintype "passive"))
      (node (ref "U5") (pin "P$2") (pinfunction "RF_IN_P$2") (pintype "bidirectional"))
    )
    (net (code "51") (name "SCLK") (class "Default")
      (node (ref "J9") (pin "P5") (pinfunction "SCLK_P5") (pintype "bidirectional"))
      (node (ref "U4") (pin "17") (pinfunction "PB5(SCK)_17") (pintype "bidirectional"))
    )
    (net (code "52") (name "SD_CD") (class "Default")
      (node (ref "JP6") (pin "2") (pinfunction "2_2") (pintype "passive"))
      (node (ref "R12") (pin "1") (pinfunction "1_1") (pintype "passive"))
      (node (ref "U4") (pin "11") (pinfunction "PD7(AIN1)_11") (pintype "bidirectional"))
    )
    (net (code "53") (name "SOFT_SERIAL_RX") (class "Default")
      (node (ref "J7") (pin "3") (pinfunction "3_3") (pintype "passive"))
      (node (ref "U4") (pin "25") (pinfunction "PC2(ADC2)_25") (pintype "bidirectional"))
    )
    (net (code "54") (name "SOFT_SERIAL_TX") (class "Default")
      (node (ref "J8") (pin "3") (pinfunction "3_3") (pintype "passive"))
      (node (ref "U4") (pin "24") (pinfunction "PC1(ADC1)_24") (pintype "bidirectional"))
    )
    (net (code "55") (name "SS") (class "Default")
      (node (ref "J9") (pin "P2") (pinfunction "CS_P2") (pintype "bidirectional"))
      (node (ref "U4") (pin "14") (pinfunction "PB2(SS/OC1B)_14") (pintype "bidirectional"))
    )
    (net (code "56") (name "UC_RESET") (class "Default")
      (node (ref "C23") (pin "2") (pinfunction "2_2") (pintype "passive"))
      (node (ref "JP5") (pin "3") (pinfunction "3_3") (pintype "passive"))
      (node (ref "R9") (pin "1") (pinfunction "1_1") (pintype "passive"))
      (node (ref "U4") (pin "29") (pinfunction "PC6(/RESET)_29") (pintype "bidirectional"))
      (node (ref "U5") (pin "P$4") (pinfunction "RESET_P$4") (pintype "bidirectional"))
    )
    (net (code "57") (name "UC_RX") (class "Default")
      (node (ref "J12") (pin "3") (pinfunction "3_3") (pintype "passive"))
      (node (ref "U4") (pin "30") (pinfunction "PD0(RXD)_30") (pintype "bidirectional"))
    )
    (net (code "58") (name "UC_TX") (class "Default")
      (node (ref "J13") (pin "3") (pinfunction "3_3") (pintype "passive"))
      (node (ref "U4") (pin "31") (pinfunction "PD1(TXD)_31") (pintype "bidirectional"))
    )
    (net (code "59") (name "USB_DM") (class "Default")
      (node (ref "IC1") (pin "16") (pinfunction "USBDM_16") (pintype "bidirectional"))
      (node (ref "J4") (pin "2") (pinfunction "D-_2") (pintype "bidirectional"))
    )
    (net (code "60") (name "USB_DP") (class "Default")
      (node (ref "IC1") (pin "15") (pinfunction "USBDP_15") (pintype "bidirectional"))
      (node (ref "J4") (pin "3") (pinfunction "D+_3") (pintype "bidirectional"))
    )
    (net (code "61") (name "USB_RX") (class "Default")
      (node (ref "IC1") (pin "5") (pinfunction "RXD_5") (pintype "input"))
      (node (ref "J13") (pin "2") (pinfunction "2_2") (pintype "passive"))
      (node (ref "TP2") (pin "P$1") (pinfunction "1_P$1") (pintype "bidirectional"))
    )
    (net (code "62") (name "USB_TX") (class "Default")
      (node (ref "IC1") (pin "1") (pinfunction "TXD_1") (pintype "output"))
      (node (ref "J12") (pin "2") (pinfunction "2_2") (pintype "passive"))
      (node (ref "TP1") (pin "P$1") (pinfunction "1_P$1") (pintype "bidirectional"))
    )
    (net (code "63") (name "USB_VCC") (class "Default")
      (node (ref "FB3") (pin "2") (pinfunction "P$2_2") (pintype "bidirectional"))
      (node (ref "J11") (pin "3") (pinfunction "3_3") (pintype "passive"))
      (node (ref "J4") (pin "1") (pinfunction "VBUS_1") (pintype "power_in"))
    )
    (net (code "64") (name "VIN") (class "Default")
      (node (ref "C1") (pin "1") (pinfunction "1_1") (pintype "passive"))
      (node (ref "C5") (pin "+") (pinfunction "+_+") (pintype "passive"))
      (node (ref "L3") (pin "P$2") (pinfunction "2_P$2") (pintype "passive"))
      (node (ref "U1") (pin "5") (pinfunction "VIN_5") (pintype "bidirectional"))
    )
    (net (code "65") (name "unconnected-(IC1-CBUS0-Pad23)") (class "Default")
      (node (ref "IC1") (pin "23") (pinfunction "CBUS0_23") (pintype "bidirectional"))
    )
    (net (code "66") (name "unconnected-(IC1-CBUS1-Pad22)") (class "Default")
      (node (ref "IC1") (pin "22") (pinfunction "CBUS1_22") (pintype "bidirectional"))
    )
    (net (code "67") (name "unconnected-(IC1-CBUS2-Pad13)") (class "Default")
      (node (ref "IC1") (pin "13") (pinfunction "CBUS2_13") (pintype "bidirectional"))
    )
    (net (code "68") (name "unconnected-(IC1-CBUS3-Pad14)") (class "Default")
      (node (ref "IC1") (pin "14") (pinfunction "CBUS3_14") (pintype "bidirectional"))
    )
    (net (code "69") (name "unconnected-(IC1-CBUS4-Pad12)") (class "Default")
      (node (ref "IC1") (pin "12") (pinfunction "CBUS4_12") (pintype "bidirectional"))
    )
    (net (code "70") (name "unconnected-(IC1-OSCI-Pad27)") (class "Default")
      (node (ref "IC1") (pin "27") (pinfunction "OSCI_27") (pintype "input"))
    )
    (net (code "71") (name "unconnected-(IC1-OSCO-Pad28)") (class "Default")
      (node (ref "IC1") (pin "28") (pinfunction "OSCO_28") (pintype "output"))
    )
    (net (code "72") (name "unconnected-(IC1-~{DCD}-Pad10)") (class "Default")
      (node (ref "IC1") (pin "10") (pinfunction "~{DCD}_10") (pintype "input"))
    )
    (net (code "73") (name "unconnected-(IC1-~{DSR}-Pad9)") (class "Default")
      (node (ref "IC1") (pin "9") (pinfunction "~{DSR}_9") (pintype "input"))
    )
    (net (code "74") (name "unconnected-(IC1-~{RESET}-Pad19)") (class "Default")
      (node (ref "IC1") (pin "19") (pinfunction "~{RESET}_19") (pintype "input"))
    )
    (net (code "75") (name "unconnected-(IC1-~{RI}-Pad6)") (class "Default")
      (node (ref "IC1") (pin "6") (pinfunction "~{RI}_6") (pintype "input"))
    )
    (net (code "76") (name "unconnected-(IC1-~{RTS}-Pad3)") (class "Default")
      (node (ref "IC1") (pin "3") (pinfunction "~{RTS}_3") (pintype "output"))
    )
    (net (code "77") (name "unconnected-(U4-ADC6-Pad19)") (class "Default")
      (node (ref "U4") (pin "19") (pinfunction "ADC6_19") (pintype "bidirectional"))
    )
    (net (code "78") (name "unconnected-(U4-ADC7-Pad22)") (class "Default")
      (node (ref "U4") (pin "22") (pinfunction "ADC7_22") (pintype "bidirectional"))
    )
    (net (code "79") (name "unconnected-(U4-PB1(OC1A)-Pad13)") (class "Default")
      (node (ref "U4") (pin "13") (pinfunction "PB1(OC1A)_13") (pintype "bidirectional"))
    )
    (net (code "80") (name "unconnected-(U4-PC0(ADC0)-Pad23)") (class "Default")
      (node (ref "U4") (pin "23") (pinfunction "PC0(ADC0)_23") (pintype "bidirectional"))
    )
    (net (code "81") (name "unconnected-(U4-PC3(ADC3)-Pad26)") (class "Default")
      (node (ref "U4") (pin "26") (pinfunction "PC3(ADC3)_26") (pintype "bidirectional"))
    )
    (net (code "82") (name "unconnected-(U4-PC4(ADC4{slash}SDA)-Pad27)") (class "Default")
      (node (ref "U4") (pin "27") (pinfunction "PC4(ADC4/SDA)_27") (pintype "bidirectional"))
    )
    (net (code "83") (name "unconnected-(U4-PC5(ADC5{slash}SCL)-Pad28)") (class "Default")
      (node (ref "U4") (pin "28") (pinfunction "PC5(ADC5/SCL)_28") (pintype "bidirectional"))
    )
    (net (code "84") (name "unconnected-(U4-PD2(INT0)-Pad32)") (class "Default")
      (node (ref "U4") (pin "32") (pinfunction "PD2(INT0)_32") (pintype "bidirectional"))
    )
    (net (code "85") (name "unconnected-(U5-I2C_CLK-PadP$13)") (class "Default")
      (node (ref "U5") (pin "P$13") (pinfunction "I2C_CLK_P$13") (pintype "bidirectional"))
    )
    (net (code "86") (name "unconnected-(U5-I2C_DIO-PadP$12)") (class "Default")
      (node (ref "U5") (pin "P$12") (pinfunction "I2C_DIO_P$12") (pintype "bidirectional"))
    )
    (net (code "87") (name "unconnected-(U5-V_BAT-PadP$6)") (class "Default")
      (node (ref "U5") (pin "P$6") (pinfunction "V_BAT_P$6") (pintype "bidirectional"))
    )
    (net (code "88") (name "unconnected-(U5-WAKE-PadP$16)") (class "Default")
      (node (ref "U5") (pin "P$16") (pinfunction "WAKE_P$16") (pintype "bidirectional"))
    )
  )
)
